# power_intg.net
KiCad netlist of a schematic drawn in Altium Designer
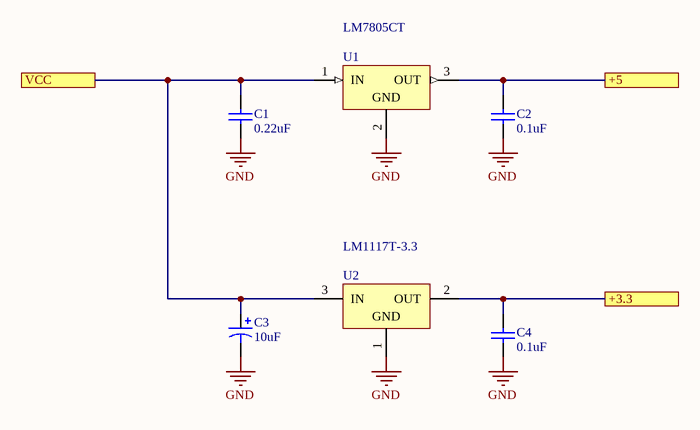
[diagram p0: power_intg.SchDoc]

(export (version "E")
  (design (tool "Eeschema 10.0.6"))
  (components
    (comp (ref "C1")
      (value "0.22uF")
      (footprint "RAD-0.1")
      (description "Capacitor")
      (fields (field (name "Comment") "Cap") (field (name "PUBLISHER") "Altium Limited"))
      (libsource (lib "Miscellaneous Devices") (part "Cap"))
    )
    (comp (ref "C2")
      (value "0.1uF")
      (footprint "RAD-0.1")
      (description "Capacitor")
      (fields (field (name "Comment") "Cap") (field (name "PUBLISHER") "Altium Limited"))
      (libsource (lib "Miscellaneous Devices") (part "Cap"))
    )
    (comp (ref "C3")
      (value "10uF")
      (footprint "RAD-0.1")
      (description "Polarized Capacitor (Radial)")
      (fields (field (name "Comment") "Cap Pol1") (field (name "PUBLISHER") "Altium Limited"))
      (libsource (lib "Miscellaneous Devices") (part "Cap Pol1"))
    )
    (comp (ref "C4")
      (value "0.1uF")
      (footprint "RAD-0.1")
      (description "Capacitor")
      (fields (field (name "Comment") "Cap") (field (name "PUBLISHER") "Altium Limited"))
      (libsource (lib "Miscellaneous Devices") (part "Cap"))
    )
    (comp (ref "U1")
      (value "LM7805CT")
      (footprint "FAIR-TO-220-3")
      (description "Positive Voltage Regulator, 5 V, 1 A, -40 to 125 degC, 3-Pin TO-220, RoHS, Tube")
      (fields (field (name "MANUFACTURER") "FairchildSemiconductor"))
      (libsource (lib "Altium Content Vault") (part "FAIR-LM7805CT-TO220-3"))
    )
    (comp (ref "U2")
      (value "LM1117T-3.3")
      (footprint "T03B")
      (description "800mA Low-Dropout Linear Regulator, 3-pin TO-220")
      (fields (field (name "MANUFACTURER") "National Semiconductor"))
      (libsource (lib "Altium Content Vault") (part "PM-REG-LM1086-SIL3"))
    )
  )
  (nets
    (net (code "1") (name "/+3.3") (class "Default")
      (node (ref "C4") (pin "1") (pinfunction "1_1") (pintype "passive"))
      (node (ref "U2") (pin "2") (pinfunction "OUT_2") (pintype "power_in"))
    )
    (net (code "2") (name "/+5") (class "Default")
      (node (ref "C2") (pin "1") (pinfunction "1_1") (pintype "passive"))
      (node (ref "U1") (pin "3") (pinfunction "OUT_3") (pintype "output"))
    )
    (net (code "3") (name "/VCC") (class "Default")
      (node (ref "C1") (pin "1") (pinfunction "1_1") (pintype "passive"))
      (node (ref "C3") (pin "1") (pinfunction "1_1") (pintype "passive"))
      (node (ref "U1") (pin "1") (pinfunction "IN_1") (pintype "input"))
      (node (ref "U2") (pin "3") (pinfunction "IN_3") (pintype "power_in"))
    )
    (net (code "4") (name "GND") (class "Default")
      (node (ref "C1") (pin "2") (pinfunction "2_2") (pintype "passive"))
      (node (ref "C2") (pin "2") (pinfunction "2_2") (pintype "passive"))
      (node (ref "C3") (pin "2") (pinfunction "2_2") (pintype "passive"))
      (node (ref "C4") (pin "2") (pinfunction "2_2") (pintype "passive"))
      (node (ref "U1") (pin "2") (pinfunction "GND_2") (pintype "power_in"))
      (node (ref "U2") (pin "1") (pinfunction "GND_1") (pintype "power_in"))
    )
  )
)
